# SCH_wifi-card_2024-06-20.net
KiCad netlist of a schematic drawn in EasyEDA
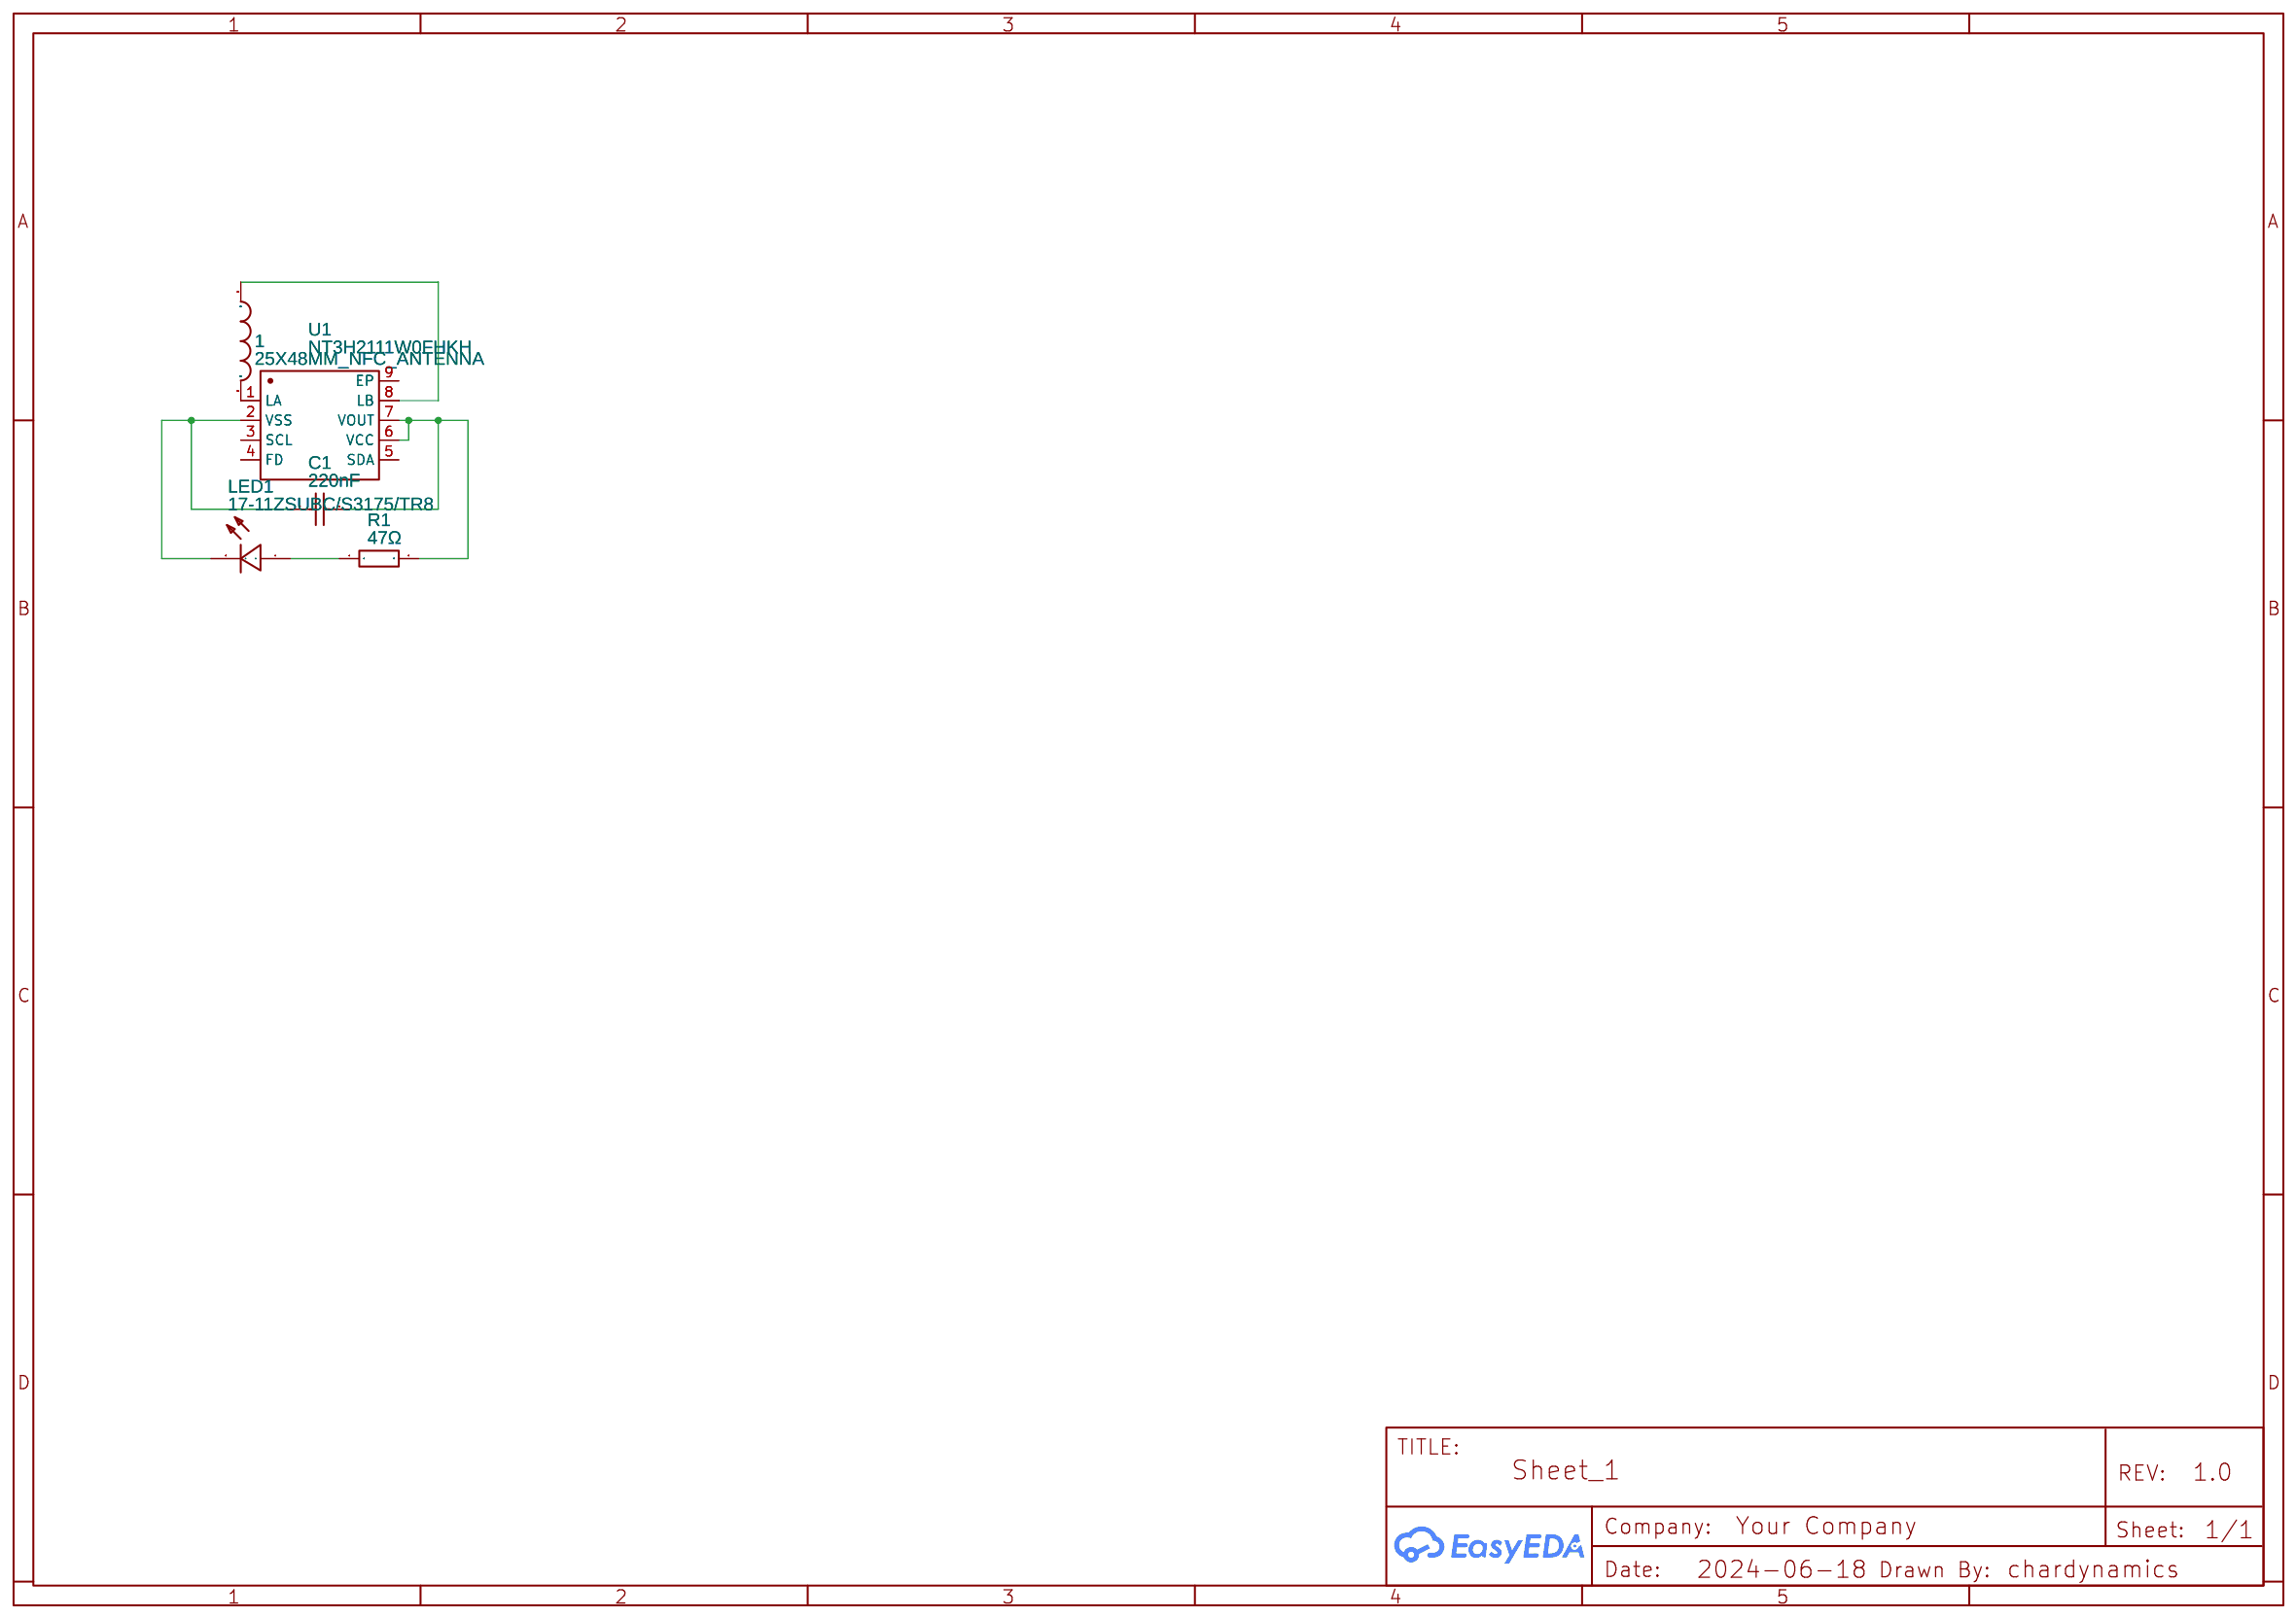
[diagram p0: schematic sheet]

(export (version "E")
  (design (tool "Eeschema 10.0.6"))
  (components
    (comp (ref "1") (value "25X48MM_NFC_ANTENNA") (libsource (lib "") (part "25X48MM_NFC_ANTENNA")))
    (comp (ref "C1")
      (value "220nF")
      (fields
        (field (name "Manufacturer Part") "CL10B224KA8NNNC")
        (field (name "Manufacturer") "SAMSUNG(三星)")
      )
      (libsource (lib "") (part "CL10B224KA8NNNC"))
    )
    (comp (ref "LED1")
      (value "17-11ZSUBC/S3175/TR8")
      (fields (field (name "Manufacturer") "EVERLIGHT(亿光)"))
      (libsource (lib "") (part "17-11ZSUBC/S3175/TR8"))
    )
    (comp (ref "R1")
      (value "47Ω")
      (fields
        (field (name "Manufacturer Part") "0603WAF470JT5E")
        (field (name "Manufacturer") "UNI-ROYAL(厚声)")
      )
      (libsource (lib "") (part "0603WAF470JT5E"))
    )
    (comp (ref "U1")
      (value "NT3H2111W0FHKH")
      (fields (field (name "Manufacturer") "NXP(恩智浦)"))
      (libsource (lib "") (part "NT3H2111W0FHKH"))
    )
  )
  (nets
    (net (code "1") (name "Net-(LED1-A)") (class "Default")
      (node (ref "LED1") (pin "1") (pinfunction "A_1") (pintype "unspecified"))
      (node (ref "R1") (pin "1") (pinfunction "1_1") (pintype "input"))
    )
    (net (code "2") (name "Net-(LED1-K)") (class "Default")
      (node (ref "C1") (pin "1") (pinfunction "1_1") (pintype "input"))
      (node (ref "LED1") (pin "2") (pinfunction "K_2") (pintype "unspecified"))
      (node (ref "U1") (pin "2") (pinfunction "VSS_2") (pintype "unspecified"))
    )
    (net (code "3") (name "Net-(U1-LA)") (class "Default")
      (node (ref "1") (pin "P$2") (pinfunction "P$2_P$2") (pintype "bidirectional"))
      (node (ref "U1") (pin "1") (pinfunction "LA_1") (pintype "unspecified"))
    )
    (net (code "4") (name "Net-(U1-LB)") (class "Default")
      (node (ref "1") (pin "P$1") (pinfunction "P$1_P$1") (pintype "bidirectional"))
      (node (ref "U1") (pin "8") (pinfunction "LB_8") (pintype "unspecified"))
    )
    (net (code "5") (name "Net-(U1-VCC)") (class "Default")
      (node (ref "C1") (pin "2") (pinfunction "2_2") (pintype "input"))
      (node (ref "R1") (pin "2") (pinfunction "2_2") (pintype "input"))
      (node (ref "U1") (pin "6") (pinfunction "VCC_6") (pintype "unspecified"))
      (node (ref "U1") (pin "7") (pinfunction "VOUT_7") (pintype "unspecified"))
    )
    (net (code "6") (name "unconnected-(U1-EP-Pad9)") (class "Default")
      (node (ref "U1") (pin "9") (pinfunction "EP_9") (pintype "unspecified"))
    )
    (net (code "7") (name "unconnected-(U1-FD-Pad4)") (class "Default")
      (node (ref "U1") (pin "4") (pinfunction "FD_4") (pintype "unspecified"))
    )
    (net (code "8") (name "unconnected-(U1-SCL-Pad3)") (class "Default")
      (node (ref "U1") (pin "3") (pinfunction "SCL_3") (pintype "unspecified"))
    )
    (net (code "9") (name "unconnected-(U1-SDA-Pad5)") (class "Default")
      (node (ref "U1") (pin "5") (pinfunction "SDA_5") (pintype "unspecified"))
    )
  )
)
